# Crutch_Light_v1p01.net
KiCad netlist of a schematic drawn in EAGLE
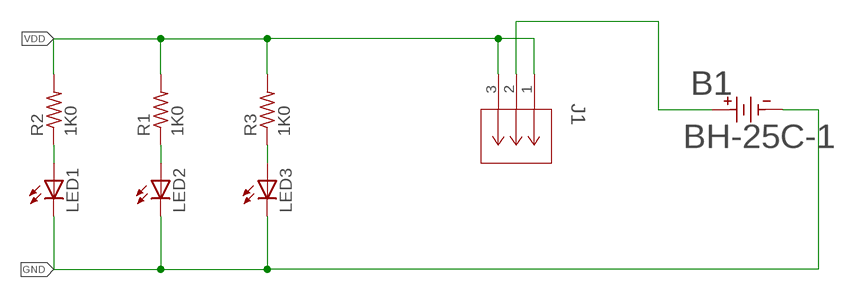
[diagram p0: schematic, sheet 1]

(export (version "E")
  (design (tool "Eeschema 10.0.6"))
  (components
    (comp (ref "B1")
      (value "BH-25C-1")
      (footprint "eagle-import:BH-25C-1_ADM")
      (fields (field (name "COPYRIGHT") "Copyright (C) 2023 Ultra Librarian. All rights reserved."))
      (libsource (lib "eagle-import") (part "BH-25C-1"))
    )
    (comp (ref "J1")
      (value "CONN_530470310_PICOBLADE_X_3")
      (footprint "eagle-import:CON_530470310_MOL")
      (fields
        (field (name "PARTNO") "530470310")
        (field (name "COPYRIGHT") "Copyright (C) 2022 Ultra Librarian. All rights reserved.")
      )
      (libsource (lib "eagle-import") (part "CONN_530470310_PICOBLADE_X_3"))
    )
    (comp (ref "LED1")
      (value "Green")
      (footprint "eagle-import:0805")
      (fields (field (name "PARTNO") "LG R971-KN-1"))
      (libsource (lib "eagle-import") (part "LED_0805_GREEN"))
    )
    (comp (ref "LED2")
      (value "Green")
      (footprint "eagle-import:0805")
      (fields (field (name "PARTNO") "LG R971-KN-1"))
      (libsource (lib "eagle-import") (part "LED_0805_GREEN"))
    )
    (comp (ref "LED3")
      (value "Green")
      (footprint "eagle-import:0805")
      (fields (field (name "PARTNO") "LG R971-KN-1"))
      (libsource (lib "eagle-import") (part "LED_0805_GREEN"))
    )
    (comp (ref "R1")
      (value "1K0")
      (footprint "eagle-import:0402")
      (fields (field (name "PARTNO") "CRG0402J1K0"))
      (libsource (lib "eagle-import") (part "R_0402_1K0"))
    )
    (comp (ref "R2")
      (value "1K0")
      (footprint "eagle-import:0402")
      (fields (field (name "PARTNO") "CRG0402J1K0"))
      (libsource (lib "eagle-import") (part "R_0402_1K0"))
    )
    (comp (ref "R3")
      (value "1K0")
      (footprint "eagle-import:0402")
      (fields (field (name "PARTNO") "CRG0402J1K0"))
      (libsource (lib "eagle-import") (part "R_0402_1K0"))
    )
  )
  (nets
    (net (code "1") (name "GND") (class "Default")
      (node (ref "B1") (pin "1") (pinfunction "1_1") (pintype "passive"))
      (node (ref "LED1") (pin "2") (pinfunction "C_2") (pintype "passive"))
      (node (ref "LED2") (pin "2") (pinfunction "C_2") (pintype "passive"))
      (node (ref "LED3") (pin "2") (pinfunction "C_2") (pintype "passive"))
    )
    (net (code "2") (name "Net-(B1-Pad2)") (class "Default")
      (node (ref "B1") (pin "2") (pinfunction "2_2") (pintype "passive"))
      (node (ref "J1") (pin "2") (pinfunction "2_2") (pintype "passive"))
    )
    (net (code "3") (name "Net-(LED1-A)") (class "Default")
      (node (ref "LED1") (pin "1") (pinfunction "A_1") (pintype "passive"))
      (node (ref "R2") (pin "P$1") (pinfunction "1_P$1") (pintype "passive"))
    )
    (net (code "4") (name "Net-(LED2-A)") (class "Default")
      (node (ref "LED2") (pin "1") (pinfunction "A_1") (pintype "passive"))
      (node (ref "R1") (pin "P$1") (pinfunction "1_P$1") (pintype "passive"))
    )
    (net (code "5") (name "Net-(LED3-A)") (class "Default")
      (node (ref "LED3") (pin "1") (pinfunction "A_1") (pintype "passive"))
      (node (ref "R3") (pin "P$1") (pinfunction "1_P$1") (pintype "passive"))
    )
    (net (code "6") (name "VDD") (class "Default")
      (node (ref "J1") (pin "1") (pinfunction "1_1") (pintype "passive"))
      (node (ref "J1") (pin "3") (pinfunction "3_3") (pintype "passive"))
      (node (ref "R1") (pin "P$2") (pinfunction "2_P$2") (pintype "passive"))
      (node (ref "R2") (pin "P$2") (pinfunction "2_P$2") (pintype "passive"))
      (node (ref "R3") (pin "P$2") (pinfunction "2_P$2") (pintype "passive"))
    )
  )
)
